# SHC_amp_fuzz.net
KiCad netlist of a schematic drawn in EasyEDA
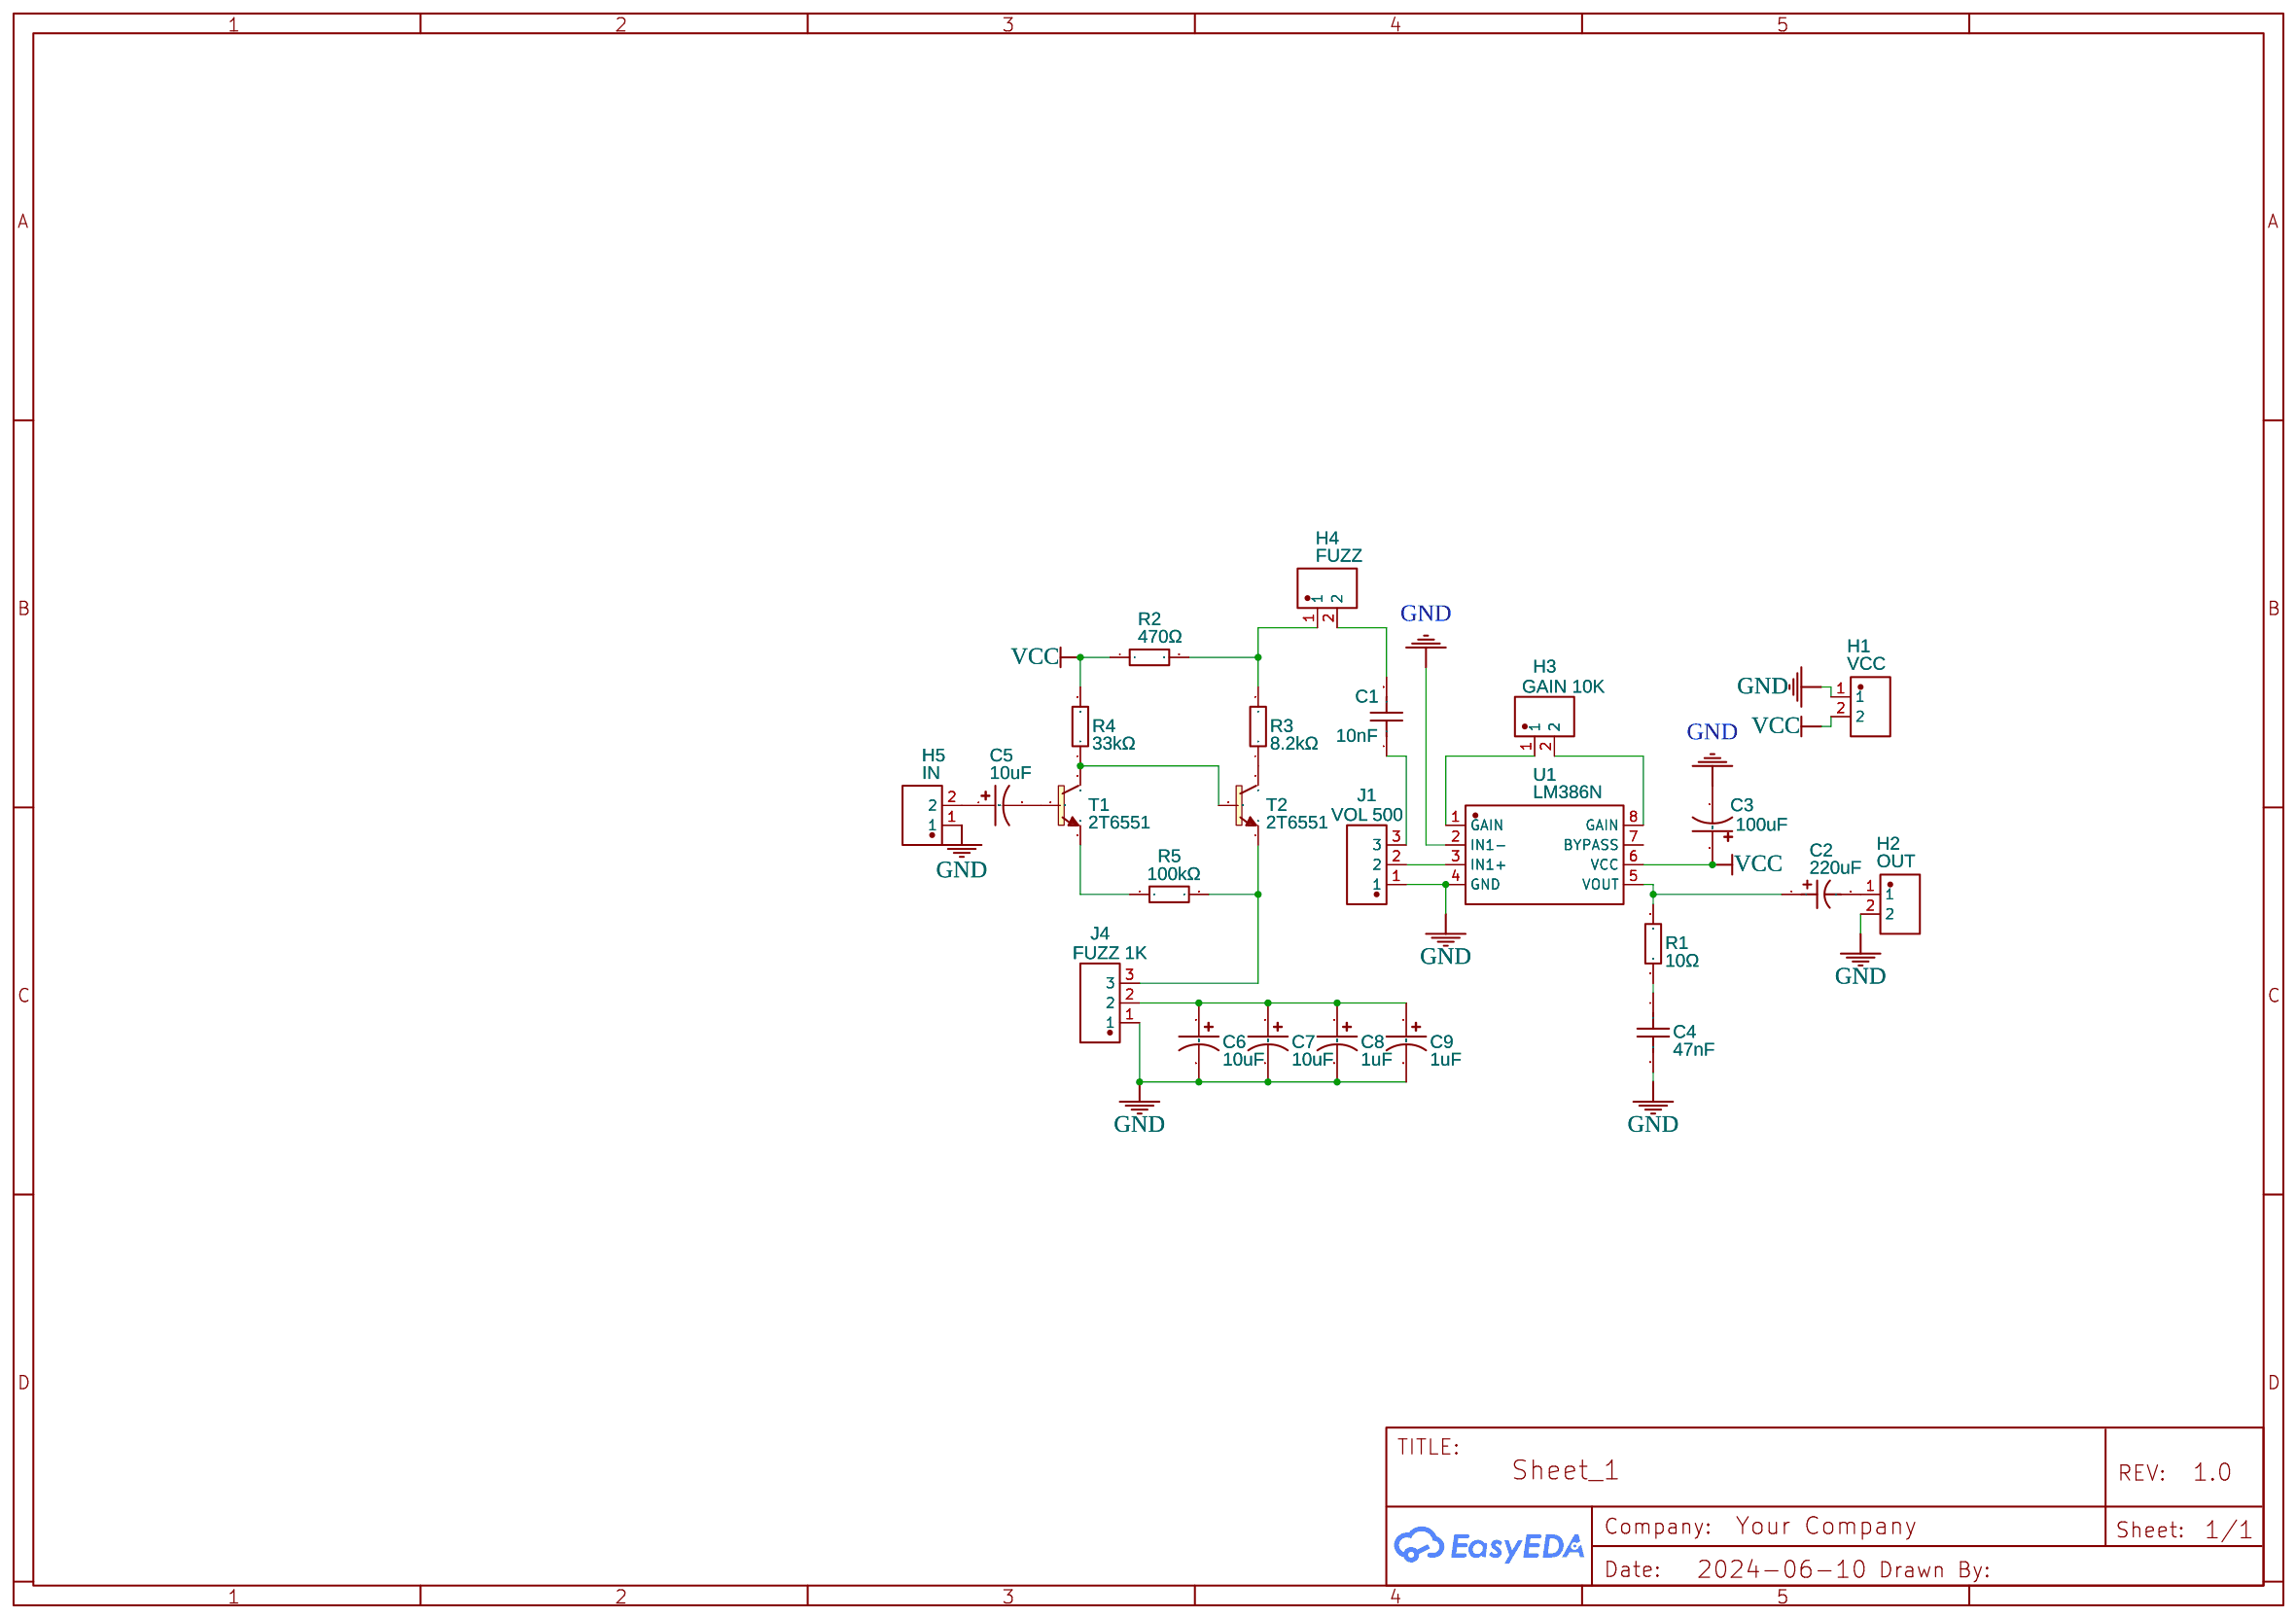
[diagram p0: schematic sheet]

(export (version "E")
  (design (tool "Eeschema 10.0.6"))
  (components
    (comp (ref "C1")
      (value "10nF")
      (fields
        (field (name "Manufacturer Part") "CC1H104ZA1PD3F5P3003")
        (field (name "Manufacturer") "Dersonic(德尔创)")
      )
      (libsource (lib "") (part "CC1H104ZA1PD3F5P3003_1"))
    )
    (comp (ref "C2")
      (value "220uF")
      (fields (field (name "Manufacturer Part") "16V470uF CD110") (field (name "Manufacturer") "HRK(鸿瑞凯电子)"))
      (libsource (lib "") (part "16V470UF CD110"))
    )
    (comp (ref "C3")
      (value "100uF")
      (fields (field (name "Manufacturer Part") "LKMC2001J101MF") (field (name "Manufacturer") "Ymin(永铭)"))
      (libsource (lib "") (part "LKMC2001J101MF"))
    )
    (comp (ref "C4")
      (value "47nF")
      (fields
        (field (name "Manufacturer Part") "CC1H104ZA1PD3F5P3003")
        (field (name "Manufacturer") "Dersonic(德尔创)")
      )
      (libsource (lib "") (part "CC1H104ZA1PD3F5P3003"))
    )
    (comp (ref "C5")
      (value "10uF")
      (fields (field (name "Manufacturer Part") "16V100uF CD288") (field (name "Manufacturer") "HRK(鸿瑞凯电子)"))
      (libsource (lib "") (part "16V100UF CD288_C2960368"))
    )
    (comp (ref "C6")
      (value "10uF")
      (fields (field (name "Manufacturer Part") "16V100uF CD288") (field (name "Manufacturer") "HRK(鸿瑞凯电子)"))
      (libsource (lib "") (part "16V100UF CD288_C2960368_1"))
    )
    (comp (ref "C7")
      (value "10uF")
      (fields (field (name "Manufacturer Part") "16V100uF CD288") (field (name "Manufacturer") "HRK(鸿瑞凯电子)"))
      (libsource (lib "") (part "16V100UF CD288_C2960368_1"))
    )
    (comp (ref "C8")
      (value "1uF")
      (fields (field (name "Manufacturer Part") "16V100uF CD288") (field (name "Manufacturer") "HRK(鸿瑞凯电子)"))
      (libsource (lib "") (part "16V100UF CD288_C2960368_1"))
    )
    (comp (ref "C9")
      (value "1uF")
      (fields (field (name "Manufacturer Part") "16V100uF CD288") (field (name "Manufacturer") "HRK(鸿瑞凯电子)"))
      (libsource (lib "") (part "16V100UF CD288_C2960368_1"))
    )
    (comp (ref "H1")
      (value "VCC")
      (fields (field (name "Manufacturer Part") "2RS1-02-G") (field (name "Manufacturer") "ADAM TECH"))
      (libsource (lib "") (part "2RS1-02-G_1"))
    )
    (comp (ref "H2")
      (value "OUT")
      (fields (field (name "Manufacturer Part") "2RS1-02-G") (field (name "Manufacturer") "ADAM TECH"))
      (libsource (lib "") (part "2RS1-02-G_1"))
    )
    (comp (ref "H3")
      (value "GAIN 10K")
      (fields (field (name "Manufacturer Part") "2RS1-02-G") (field (name "Manufacturer") "ADAM TECH"))
      (libsource (lib "") (part "2RS1-02-G"))
    )
    (comp (ref "H4")
      (value "FUZZ")
      (fields (field (name "Manufacturer Part") "2RS1-02-G") (field (name "Manufacturer") "ADAM TECH"))
      (libsource (lib "") (part "2RS1-02-G"))
    )
    (comp (ref "H5")
      (value "IN")
      (fields (field (name "Manufacturer Part") "2RS1-02-G") (field (name "Manufacturer") "ADAM TECH"))
      (libsource (lib "") (part "2RS1-02-G_2"))
    )
    (comp (ref "J1")
      (value "VOL 500")
      (fields
        (field (name "Manufacturer Part") "5-535541-1")
        (field (name "Manufacturer") "TE Connectivity(泰科电子)")
      )
      (libsource (lib "") (part "5-535541-1"))
    )
    (comp (ref "J4")
      (value "FUZZ 1K")
      (fields
        (field (name "Manufacturer Part") "5-535541-1")
        (field (name "Manufacturer") "TE Connectivity(泰科电子)")
      )
      (libsource (lib "") (part "5-535541-1"))
    )
    (comp (ref "R1")
      (value "10Ω")
      (fields (field (name "Manufacturer Part") "CF1W-360Ω±5% T") (field (name "Manufacturer") "CCO(千志电子)"))
      (libsource (lib "") (part "CF1W-360Ω±5% T"))
    )
    (comp (ref "R2")
      (value "470Ω")
      (fields
        (field (name "Manufacturer Part") "CF1/4W-110KΩ±5% T52")
        (field (name "Manufacturer") "CCO(千志电子)")
      )
      (libsource (lib "") (part "CF1/4W-110KΩ±5% T52_1"))
    )
    (comp (ref "R3")
      (value "8.2kΩ")
      (fields
        (field (name "Manufacturer Part") "CF1/4W-110KΩ±5% T52")
        (field (name "Manufacturer") "CCO(千志电子)")
      )
      (libsource (lib "") (part "CF1/4W-110KΩ±5% T52"))
    )
    (comp (ref "R4")
      (value "33kΩ")
      (fields
        (field (name "Manufacturer Part") "CF1/4W-110KΩ±5% T52")
        (field (name "Manufacturer") "CCO(千志电子)")
      )
      (libsource (lib "") (part "CF1/4W-110KΩ±5% T52"))
    )
    (comp (ref "R5")
      (value "100kΩ")
      (fields
        (field (name "Manufacturer Part") "CF1/4W-110KΩ±5% T52")
        (field (name "Manufacturer") "CCO(千志电子)")
      )
      (libsource (lib "") (part "CF1/4W-110KΩ±5% T52_1"))
    )
    (comp (ref "T1") (value "2T6551") (libsource (lib "") (part "*-NPN-TO5")))
    (comp (ref "T2") (value "2T6551") (libsource (lib "") (part "*-NPN-TO5")))
    (comp (ref "U1")
      (value "LM386N")
      (fields (field (name "Manufacturer") "HTC"))
      (libsource (lib "") (part "LM386N"))
    )
  )
  (nets
    (net (code "1") (name "GND") (class "Default")
      (node (ref "C3") (pin "2") (pinfunction "2_2") (pintype "unspecified"))
      (node (ref "C4") (pin "2") (pinfunction "2_2") (pintype "unspecified"))
      (node (ref "C6") (pin "2") (pinfunction "2_2") (pintype "unspecified"))
      (node (ref "C7") (pin "2") (pinfunction "2_2") (pintype "unspecified"))
      (node (ref "C8") (pin "2") (pinfunction "2_2") (pintype "unspecified"))
      (node (ref "C9") (pin "2") (pinfunction "2_2") (pintype "unspecified"))
      (node (ref "H1") (pin "1") (pinfunction "1_1") (pintype "unspecified"))
      (node (ref "H2") (pin "2") (pinfunction "2_2") (pintype "unspecified"))
      (node (ref "H5") (pin "1") (pinfunction "1_1") (pintype "unspecified"))
      (node (ref "J1") (pin "1") (pinfunction "1_1") (pintype "unspecified"))
      (node (ref "J4") (pin "1") (pinfunction "1_1") (pintype "unspecified"))
      (node (ref "U1") (pin "2") (pinfunction "IN1-_2") (pintype "unspecified"))
      (node (ref "U1") (pin "4") (pinfunction "GND_4") (pintype "unspecified"))
    )
    (net (code "2") (name "Net-(C1-Pad1)") (class "Default")
      (node (ref "C1") (pin "1") (pinfunction "1_1") (pintype "unspecified"))
      (node (ref "J1") (pin "3") (pinfunction "3_3") (pintype "unspecified"))
    )
    (net (code "3") (name "Net-(C1-Pad2)") (class "Default")
      (node (ref "C1") (pin "2") (pinfunction "2_2") (pintype "unspecified"))
      (node (ref "H4") (pin "2") (pinfunction "2_2") (pintype "unspecified"))
    )
    (net (code "4") (name "Net-(C2-Pad2)") (class "Default")
      (node (ref "C2") (pin "2") (pinfunction "2_2") (pintype "input"))
      (node (ref "H2") (pin "1") (pinfunction "1_1") (pintype "unspecified"))
    )
    (net (code "5") (name "Net-(C4-Pad1)") (class "Default")
      (node (ref "C4") (pin "1") (pinfunction "1_1") (pintype "unspecified"))
      (node (ref "R1") (pin "1") (pinfunction "1_1") (pintype "unspecified"))
    )
    (net (code "6") (name "Net-(C5-Pad1)") (class "Default")
      (node (ref "C5") (pin "1") (pinfunction "1_1") (pintype "unspecified"))
      (node (ref "H5") (pin "2") (pinfunction "2_2") (pintype "unspecified"))
    )
    (net (code "7") (name "Net-(C6-Pad1)") (class "Default")
      (node (ref "C6") (pin "1") (pinfunction "1_1") (pintype "unspecified"))
      (node (ref "C7") (pin "1") (pinfunction "1_1") (pintype "unspecified"))
      (node (ref "C8") (pin "1") (pinfunction "1_1") (pintype "unspecified"))
      (node (ref "C9") (pin "1") (pinfunction "1_1") (pintype "unspecified"))
      (node (ref "J4") (pin "2") (pinfunction "2_2") (pintype "unspecified"))
    )
    (net (code "8") (name "Net-(H3-Pad1)") (class "Default")
      (node (ref "H3") (pin "1") (pinfunction "1_1") (pintype "unspecified"))
      (node (ref "U1") (pin "1") (pinfunction "GAIN_1") (pintype "unspecified"))
    )
    (net (code "9") (name "Net-(H3-Pad2)") (class "Default")
      (node (ref "H3") (pin "2") (pinfunction "2_2") (pintype "unspecified"))
      (node (ref "U1") (pin "8") (pinfunction "GAIN_8") (pintype "unspecified"))
    )
    (net (code "10") (name "Net-(H4-Pad1)") (class "Default")
      (node (ref "H4") (pin "1") (pinfunction "1_1") (pintype "unspecified"))
      (node (ref "R2") (pin "2") (pinfunction "2_2") (pintype "unspecified"))
      (node (ref "R3") (pin "2") (pinfunction "2_2") (pintype "unspecified"))
    )
    (net (code "11") (name "Net-(T1-B)") (class "Default")
      (node (ref "C5") (pin "2") (pinfunction "2_2") (pintype "unspecified"))
      (node (ref "T1") (pin "2") (pinfunction "B_2") (pintype "bidirectional"))
    )
    (net (code "12") (name "Net-(T1-C)") (class "Default")
      (node (ref "R4") (pin "1") (pinfunction "1_1") (pintype "unspecified"))
      (node (ref "T1") (pin "3") (pinfunction "C_3") (pintype "bidirectional"))
      (node (ref "T2") (pin "2") (pinfunction "B_2") (pintype "bidirectional"))
    )
    (net (code "13") (name "Net-(T1-E)") (class "Default")
      (node (ref "R5") (pin "1") (pinfunction "1_1") (pintype "unspecified"))
      (node (ref "T1") (pin "1") (pinfunction "E_1") (pintype "bidirectional"))
    )
    (net (code "14") (name "Net-(T2-C)") (class "Default")
      (node (ref "R3") (pin "1") (pinfunction "1_1") (pintype "unspecified"))
      (node (ref "T2") (pin "3") (pinfunction "C_3") (pintype "bidirectional"))
    )
    (net (code "15") (name "Net-(T2-E)") (class "Default")
      (node (ref "J4") (pin "3") (pinfunction "3_3") (pintype "unspecified"))
      (node (ref "R5") (pin "2") (pinfunction "2_2") (pintype "unspecified"))
      (node (ref "T2") (pin "1") (pinfunction "E_1") (pintype "bidirectional"))
    )
    (net (code "16") (name "Net-(U1-IN1+)") (class "Default")
      (node (ref "J1") (pin "2") (pinfunction "2_2") (pintype "unspecified"))
      (node (ref "U1") (pin "3") (pinfunction "IN1+_3") (pintype "unspecified"))
    )
    (net (code "17") (name "Net-(U1-VOUT)") (class "Default")
      (node (ref "C2") (pin "1") (pinfunction "1_1") (pintype "input"))
      (node (ref "R1") (pin "2") (pinfunction "2_2") (pintype "unspecified"))
      (node (ref "U1") (pin "5") (pinfunction "VOUT_5") (pintype "unspecified"))
    )
    (net (code "18") (name "VCC") (class "Default")
      (node (ref "C3") (pin "1") (pinfunction "1_1") (pintype "unspecified"))
      (node (ref "H1") (pin "2") (pinfunction "2_2") (pintype "unspecified"))
      (node (ref "R2") (pin "1") (pinfunction "1_1") (pintype "unspecified"))
      (node (ref "R4") (pin "2") (pinfunction "2_2") (pintype "unspecified"))
      (node (ref "U1") (pin "6") (pinfunction "VCC_6") (pintype "unspecified"))
    )
    (net (code "19") (name "unconnected-(U1-BYPASS-Pad7)") (class "Default")
      (node (ref "U1") (pin "7") (pinfunction "BYPASS_7") (pintype "unspecified"))
    )
  )
)
